# MS5837_Breakout.net
KiCad netlist of a schematic drawn in EAGLE
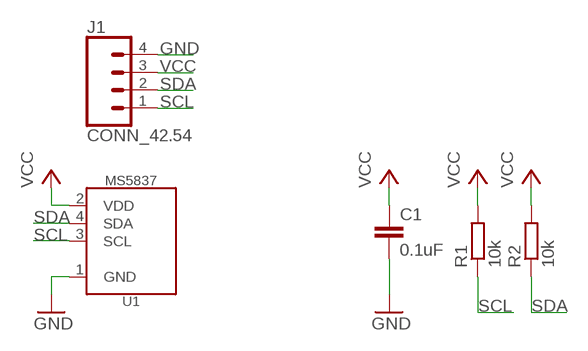
[diagram p0: schematic, sheet 1]

(export (version "E")
  (design (tool "Eeschema 10.0.6"))
  (components
    (comp (ref "C1")
      (value "0.1uF")
      (footprint "eagle-import:C0805")
      (libsource (lib "eagle-import") (part "C-EUC0805"))
    )
    (comp (ref "J1")
      (value "CONN_42.54")
      (footprint "eagle-import:1X04")
      (libsource (lib "eagle-import") (part "CONN_42.54"))
    )
    (comp (ref "R1")
      (value "10k")
      (footprint "eagle-import:R0805")
      (fields (field (name "MF") "Panasonic") (field (name "MPN") "ERA-6AEB105V"))
      (libsource (lib "eagle-import") (part "R-EU_R0805P1M"))
    )
    (comp (ref "R2")
      (value "10k")
      (footprint "eagle-import:R0805")
      (fields (field (name "MF") "Panasonic") (field (name "MPN") "ERA-6AEB105V"))
      (libsource (lib "eagle-import") (part "R-EU_R0805P1M"))
    )
    (comp (ref "U1")
      (value "MS5837")
      (footprint "eagle-import:MS5837")
      (libsource (lib "eagle-import") (part "MS5837"))
    )
  )
  (nets
    (net (code "1") (name "/SCL") (class "Default")
      (node (ref "J1") (pin "1") (pinfunction "1_1") (pintype "passive"))
      (node (ref "R1") (pin "1") (pinfunction "1_1") (pintype "passive"))
      (node (ref "U1") (pin "3") (pinfunction "SCL_3") (pintype "input"))
    )
    (net (code "2") (name "/SDA") (class "Default")
      (node (ref "J1") (pin "2") (pinfunction "2_2") (pintype "passive"))
      (node (ref "R2") (pin "1") (pinfunction "1_1") (pintype "passive"))
      (node (ref "U1") (pin "4") (pinfunction "SDA_4") (pintype "bidirectional"))
    )
    (net (code "3") (name "GND") (class "Default")
      (node (ref "C1") (pin "2") (pinfunction "2_2") (pintype "passive"))
      (node (ref "J1") (pin "4") (pinfunction "4_4") (pintype "passive"))
      (node (ref "U1") (pin "1") (pinfunction "GND_1") (pintype "power_in"))
    )
    (net (code "4") (name "VCC") (class "Default")
      (node (ref "C1") (pin "1") (pinfunction "1_1") (pintype "passive"))
      (node (ref "J1") (pin "3") (pinfunction "3_3") (pintype "passive"))
      (node (ref "R1") (pin "2") (pinfunction "2_2") (pintype "passive"))
      (node (ref "R2") (pin "2") (pinfunction "2_2") (pintype "passive"))
      (node (ref "U1") (pin "2") (pinfunction "VDD_2") (pintype "power_in"))
    )
  )
)
